# Current_Detection_9_16.net
KiCad netlist of a schematic drawn in Altium Designer
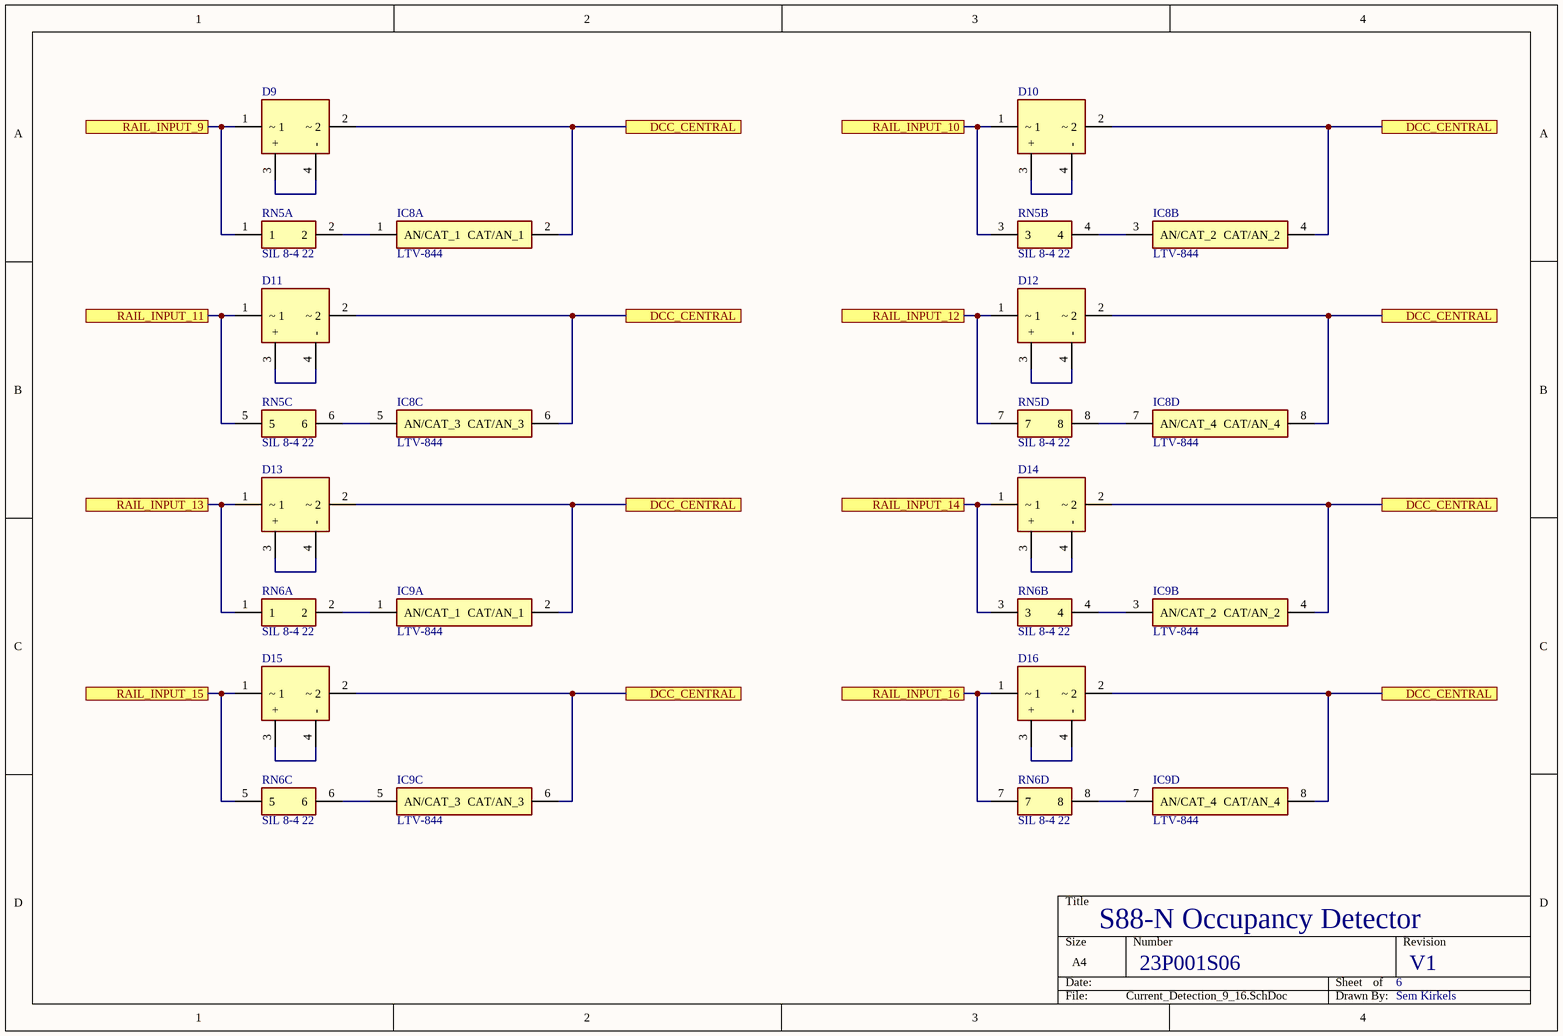
[diagram p0: Current_Detection_9_16.SchDoc]

(export (version "E")
  (design (tool "Eeschema 10.0.6"))
  (components
    (comp (ref "D9")
      (value "B140C1000DIP_DB101")
      (footprint "FBR_B140C1000DIP")
      (description "Bridge Rectifier")
      (fields
        (field (name "MANUFACTURER_PART_NUMBER") "DB101")
        (field (name "MOUSER PART NUMBER") "583-DB101")
      )
      (libsource (lib "Schematic_Library_S88N") (part "B140C1000DIP_DB101"))
    )
    (comp (ref "D10")
      (value "B140C1000DIP_DB101")
      (footprint "FBR_B140C1000DIP")
      (description "Bridge Rectifier")
      (fields
        (field (name "MANUFACTURER_PART_NUMBER") "DB101")
        (field (name "MOUSER PART NUMBER") "583-DB101")
      )
      (libsource (lib "Schematic_Library_S88N") (part "B140C1000DIP_DB101"))
    )
    (comp (ref "D11")
      (value "B140C1000DIP_DB101")
      (footprint "FBR_B140C1000DIP")
      (description "Bridge Rectifier")
      (fields
        (field (name "MANUFACTURER_PART_NUMBER") "DB101")
        (field (name "MOUSER PART NUMBER") "583-DB101")
      )
      (libsource (lib "Schematic_Library_S88N") (part "B140C1000DIP_DB101"))
    )
    (comp (ref "D12")
      (value "B140C1000DIP_DB101")
      (footprint "FBR_B140C1000DIP")
      (description "Bridge Rectifier")
      (fields
        (field (name "MANUFACTURER_PART_NUMBER") "DB101")
        (field (name "MOUSER PART NUMBER") "583-DB101")
      )
      (libsource (lib "Schematic_Library_S88N") (part "B140C1000DIP_DB101"))
    )
    (comp (ref "D13")
      (value "B140C1000DIP_DB101")
      (footprint "FBR_B140C1000DIP")
      (description "Bridge Rectifier")
      (fields
        (field (name "MANUFACTURER_PART_NUMBER") "DB101")
        (field (name "MOUSER PART NUMBER") "583-DB101")
      )
      (libsource (lib "Schematic_Library_S88N") (part "B140C1000DIP_DB101"))
    )
    (comp (ref "D14")
      (value "B140C1000DIP_DB101")
      (footprint "FBR_B140C1000DIP")
      (description "Bridge Rectifier")
      (fields
        (field (name "MANUFACTURER_PART_NUMBER") "DB101")
        (field (name "MOUSER PART NUMBER") "583-DB101")
      )
      (libsource (lib "Schematic_Library_S88N") (part "B140C1000DIP_DB101"))
    )
    (comp (ref "D15")
      (value "B140C1000DIP_DB101")
      (footprint "FBR_B140C1000DIP")
      (description "Bridge Rectifier")
      (fields
        (field (name "MANUFACTURER_PART_NUMBER") "DB101")
        (field (name "MOUSER PART NUMBER") "583-DB101")
      )
      (libsource (lib "Schematic_Library_S88N") (part "B140C1000DIP_DB101"))
    )
    (comp (ref "D16")
      (value "B140C1000DIP_DB101")
      (footprint "FBR_B140C1000DIP")
      (description "Bridge Rectifier")
      (fields
        (field (name "MANUFACTURER_PART_NUMBER") "DB101")
        (field (name "MOUSER PART NUMBER") "583-DB101")
      )
      (libsource (lib "Schematic_Library_S88N") (part "B140C1000DIP_DB101"))
    )
    (comp (ref "IC8")
      (value "LTV-844")
      (footprint "CD4014")
      (description "Integrated Circuit")
      (fields (field (name "MOUSER PART NUMBER") "859-LTV-844"))
      (libsource (lib "Schematic_Library_S88N") (part "LTV-844"))
    )
    (comp (ref "IC9")
      (value "LTV-844")
      (footprint "CD4014")
      (description "Integrated Circuit")
      (fields (field (name "MOUSER PART NUMBER") "859-LTV-844"))
      (libsource (lib "Schematic_Library_S88N") (part "LTV-844"))
    )
    (comp (ref "RN5")
      (value "SIL 8-4 22")
      (footprint "SIL 8-4")
      (description "Resistor Network")
      (fields
        (field (name "MANUFACTURER_PART_NUMBER") "4608X-102-102LF")
        (field (name "MOUSER PART NUMBER") "652-4608X-2LF-1K")
      )
      (libsource (lib "Schematic_Library_S88N") (part "SIL 8-4 22"))
    )
    (comp (ref "RN6")
      (value "SIL 8-4 22")
      (footprint "SIL 8-4")
      (description "Resistor Network")
      (fields
        (field (name "MANUFACTURER_PART_NUMBER") "4608X-102-102LF")
        (field (name "MOUSER PART NUMBER") "652-4608X-2LF-1K")
      )
      (libsource (lib "Schematic_Library_S88N") (part "SIL 8-4 22"))
    )
  )
  (nets
    (net (code "1") (name "/DCC_CENTRAL") (class "Default")
      (node (ref "D10") (pin "2") (pinfunction "~_2_2") (pintype "passive"))
      (node (ref "D11") (pin "2") (pinfunction "~_2_2") (pintype "passive"))
      (node (ref "D12") (pin "2") (pinfunction "~_2_2") (pintype "passive"))
      (node (ref "D13") (pin "2") (pinfunction "~_2_2") (pintype "passive"))
      (node (ref "D14") (pin "2") (pinfunction "~_2_2") (pintype "passive"))
      (node (ref "D15") (pin "2") (pinfunction "~_2_2") (pintype "passive"))
      (node (ref "D16") (pin "2") (pinfunction "~_2_2") (pintype "passive"))
      (node (ref "D9") (pin "2") (pinfunction "~_2_2") (pintype "passive"))
      (node (ref "IC8") (pin "2") (pinfunction "CAT/AN_1_2") (pintype "passive"))
      (node (ref "IC8") (pin "4") (pinfunction "CAT/AN_2_4") (pintype "passive"))
      (node (ref "IC8") (pin "6") (pinfunction "CAT/AN_3_6") (pintype "passive"))
      (node (ref "IC8") (pin "8") (pinfunction "CAT/AN_4_8") (pintype "passive"))
      (node (ref "IC9") (pin "2") (pinfunction "CAT/AN_1_2") (pintype "passive"))
      (node (ref "IC9") (pin "4") (pinfunction "CAT/AN_2_4") (pintype "passive"))
      (node (ref "IC9") (pin "6") (pinfunction "CAT/AN_3_6") (pintype "passive"))
      (node (ref "IC9") (pin "8") (pinfunction "CAT/AN_4_8") (pintype "passive"))
    )
    (net (code "2") (name "/RAIL_INPUT_9") (class "Default")
      (node (ref "D9") (pin "1") (pinfunction "~_1_1") (pintype "passive"))
      (node (ref "RN5") (pin "1") (pinfunction "1_1") (pintype "passive"))
    )
    (net (code "3") (name "/RAIL_INPUT_10") (class "Default")
      (node (ref "D10") (pin "1") (pinfunction "~_1_1") (pintype "passive"))
      (node (ref "RN5") (pin "3") (pinfunction "3_3") (pintype "passive"))
    )
    (net (code "4") (name "/RAIL_INPUT_11") (class "Default")
      (node (ref "D11") (pin "1") (pinfunction "~_1_1") (pintype "passive"))
      (node (ref "RN5") (pin "5") (pinfunction "5_5") (pintype "passive"))
    )
    (net (code "5") (name "/RAIL_INPUT_12") (class "Default")
      (node (ref "D12") (pin "1") (pinfunction "~_1_1") (pintype "passive"))
      (node (ref "RN5") (pin "7") (pinfunction "7_7") (pintype "passive"))
    )
    (net (code "6") (name "/RAIL_INPUT_13") (class "Default")
      (node (ref "D13") (pin "1") (pinfunction "~_1_1") (pintype "passive"))
      (node (ref "RN6") (pin "1") (pinfunction "1_1") (pintype "passive"))
    )
    (net (code "7") (name "/RAIL_INPUT_14") (class "Default")
      (node (ref "D14") (pin "1") (pinfunction "~_1_1") (pintype "passive"))
      (node (ref "RN6") (pin "3") (pinfunction "3_3") (pintype "passive"))
    )
    (net (code "8") (name "/RAIL_INPUT_15") (class "Default")
      (node (ref "D15") (pin "1") (pinfunction "~_1_1") (pintype "passive"))
      (node (ref "RN6") (pin "5") (pinfunction "5_5") (pintype "passive"))
    )
    (net (code "9") (name "/RAIL_INPUT_16") (class "Default")
      (node (ref "D16") (pin "1") (pinfunction "~_1_1") (pintype "passive"))
      (node (ref "RN6") (pin "7") (pinfunction "7_7") (pintype "passive"))
    )
    (net (code "10") (name "Net-(D9-+)") (class "Default")
      (node (ref "D9") (pin "3") (pinfunction "+_3") (pintype "passive"))
      (node (ref "D9") (pin "4") (pinfunction "-_4") (pintype "passive"))
    )
    (net (code "11") (name "Net-(D10-+)") (class "Default")
      (node (ref "D10") (pin "3") (pinfunction "+_3") (pintype "passive"))
      (node (ref "D10") (pin "4") (pinfunction "-_4") (pintype "passive"))
    )
    (net (code "12") (name "Net-(D11-+)") (class "Default")
      (node (ref "D11") (pin "3") (pinfunction "+_3") (pintype "passive"))
      (node (ref "D11") (pin "4") (pinfunction "-_4") (pintype "passive"))
    )
    (net (code "13") (name "Net-(D12-+)") (class "Default")
      (node (ref "D12") (pin "3") (pinfunction "+_3") (pintype "passive"))
      (node (ref "D12") (pin "4") (pinfunction "-_4") (pintype "passive"))
    )
    (net (code "14") (name "Net-(D13-+)") (class "Default")
      (node (ref "D13") (pin "3") (pinfunction "+_3") (pintype "passive"))
      (node (ref "D13") (pin "4") (pinfunction "-_4") (pintype "passive"))
    )
    (net (code "15") (name "Net-(D14-+)") (class "Default")
      (node (ref "D14") (pin "3") (pinfunction "+_3") (pintype "passive"))
      (node (ref "D14") (pin "4") (pinfunction "-_4") (pintype "passive"))
    )
    (net (code "16") (name "Net-(D15-+)") (class "Default")
      (node (ref "D15") (pin "3") (pinfunction "+_3") (pintype "passive"))
      (node (ref "D15") (pin "4") (pinfunction "-_4") (pintype "passive"))
    )
    (net (code "17") (name "Net-(D16-+)") (class "Default")
      (node (ref "D16") (pin "3") (pinfunction "+_3") (pintype "passive"))
      (node (ref "D16") (pin "4") (pinfunction "-_4") (pintype "passive"))
    )
    (net (code "18") (name "Net-(IC8A-AN{slash}CAT_1)") (class "Default")
      (node (ref "IC8") (pin "1") (pinfunction "AN/CAT_1_1") (pintype "passive"))
      (node (ref "RN5") (pin "2") (pinfunction "2_2") (pintype "passive"))
    )
    (net (code "19") (name "Net-(IC8B-AN{slash}CAT_2)") (class "Default")
      (node (ref "IC8") (pin "3") (pinfunction "AN/CAT_2_3") (pintype "passive"))
      (node (ref "RN5") (pin "4") (pinfunction "4_4") (pintype "passive"))
    )
    (net (code "20") (name "Net-(IC8C-AN{slash}CAT_3)") (class "Default")
      (node (ref "IC8") (pin "5") (pinfunction "AN/CAT_3_5") (pintype "passive"))
      (node (ref "RN5") (pin "6") (pinfunction "6_6") (pintype "passive"))
    )
    (net (code "21") (name "Net-(IC8D-AN{slash}CAT_4)") (class "Default")
      (node (ref "IC8") (pin "7") (pinfunction "AN/CAT_4_7") (pintype "passive"))
      (node (ref "RN5") (pin "8") (pinfunction "8_8") (pintype "passive"))
    )
    (net (code "22") (name "Net-(IC9A-AN{slash}CAT_1)") (class "Default")
      (node (ref "IC9") (pin "1") (pinfunction "AN/CAT_1_1") (pintype "passive"))
      (node (ref "RN6") (pin "2") (pinfunction "2_2") (pintype "passive"))
    )
    (net (code "23") (name "Net-(IC9B-AN{slash}CAT_2)") (class "Default")
      (node (ref "IC9") (pin "3") (pinfunction "AN/CAT_2_3") (pintype "passive"))
      (node (ref "RN6") (pin "4") (pinfunction "4_4") (pintype "passive"))
    )
    (net (code "24") (name "Net-(IC9C-AN{slash}CAT_3)") (class "Default")
      (node (ref "IC9") (pin "5") (pinfunction "AN/CAT_3_5") (pintype "passive"))
      (node (ref "RN6") (pin "6") (pinfunction "6_6") (pintype "passive"))
    )
    (net (code "25") (name "Net-(IC9D-AN{slash}CAT_4)") (class "Default")
      (node (ref "IC9") (pin "7") (pinfunction "AN/CAT_4_7") (pintype "passive"))
      (node (ref "RN6") (pin "8") (pinfunction "8_8") (pintype "passive"))
    )
  )
)
